# leds.net
KiCad netlist of a schematic drawn in EAGLE
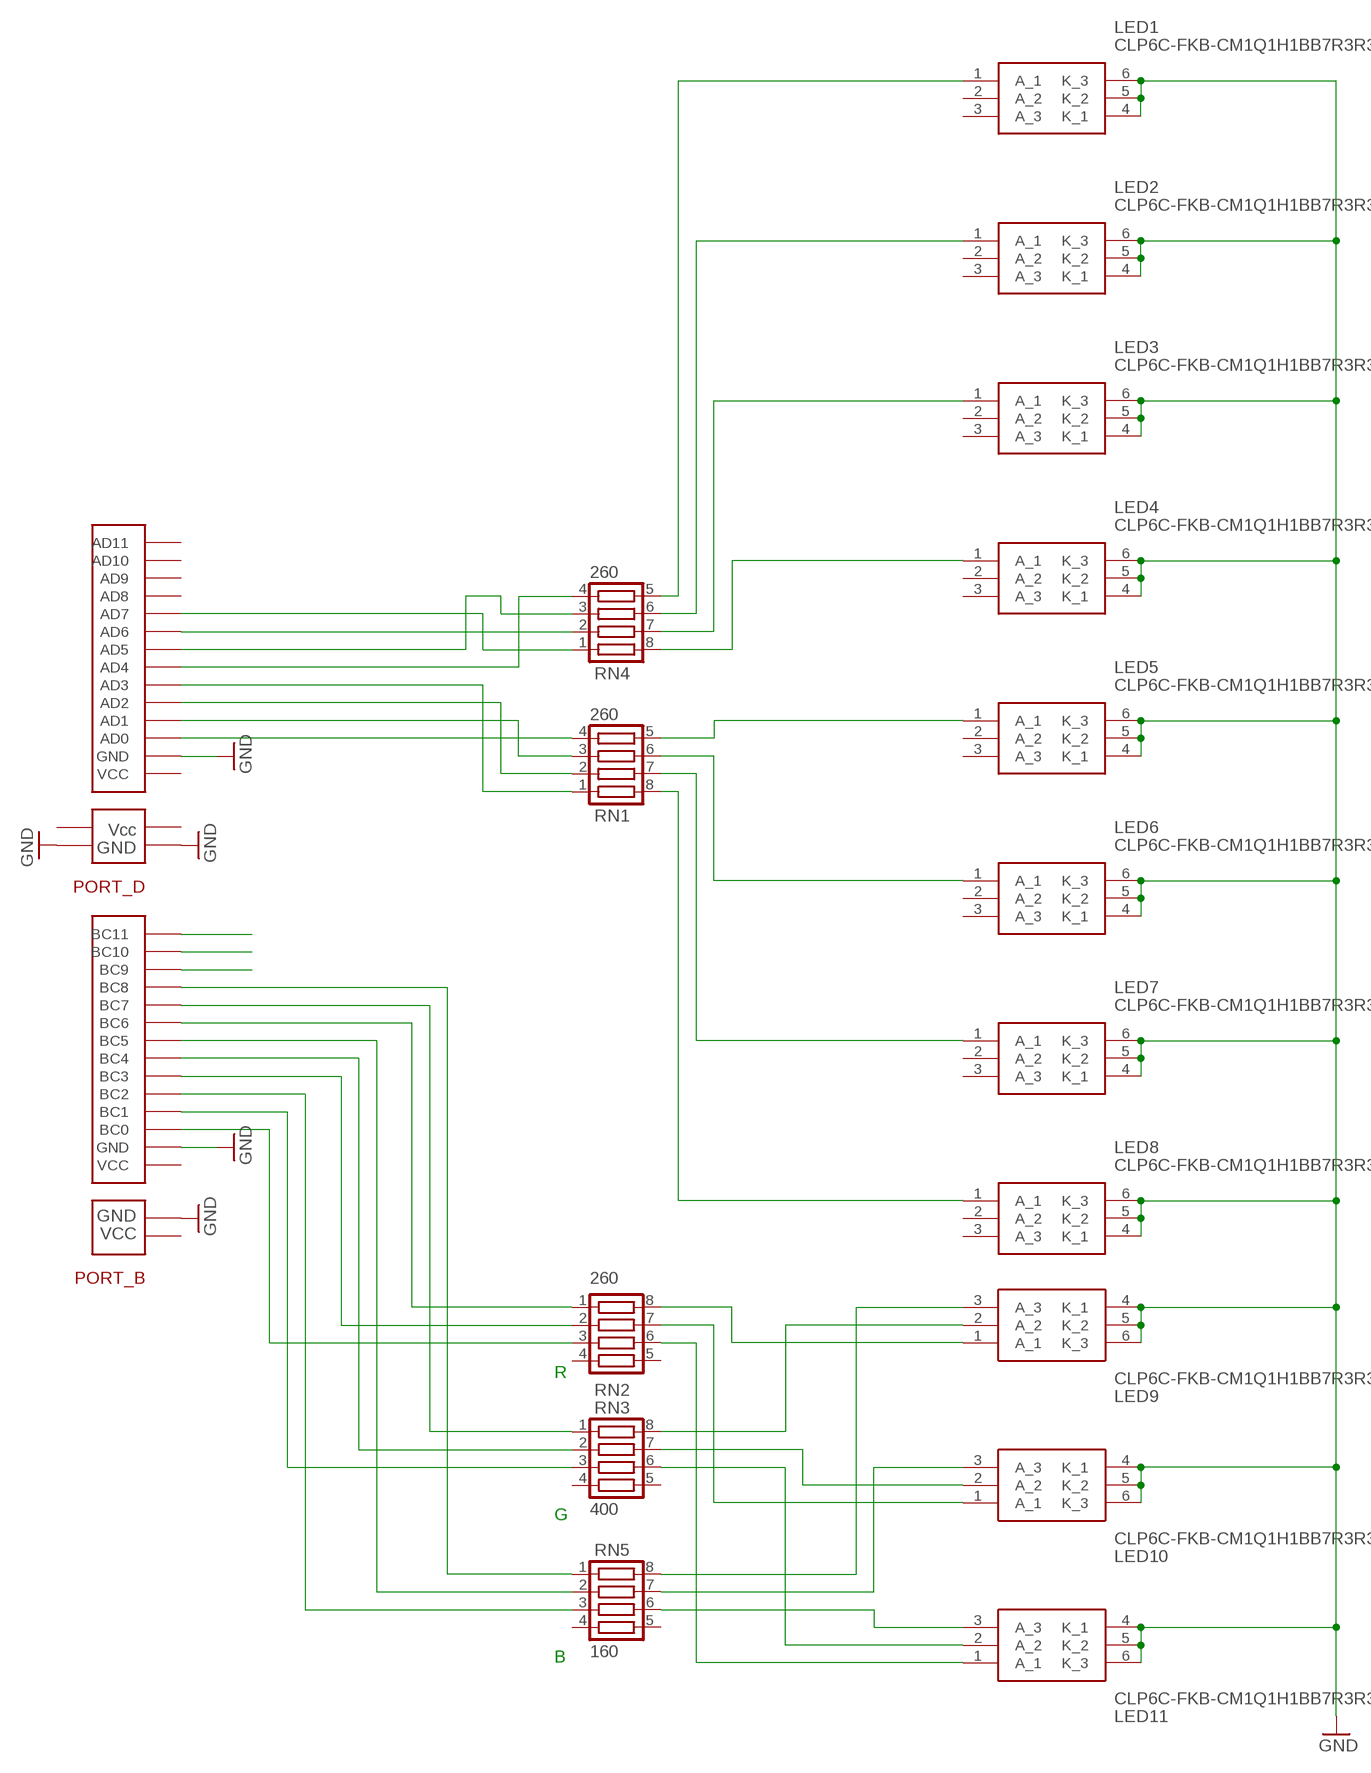
[diagram p0: schematic, sheet 1]

(export (version "E")
  (design (tool "Eeschema 10.0.6"))
  (components
    (comp (ref "LED1")
      (value "CLP6C-FKB-CM1Q1H1BB7R3R3")
      (footprint "eagle-import:CLP6CFKBCM1Q1H1BB7R3R3")
      (fields
        (field (name "MOUSER_PART_NUMBER") "941-P6CFKBCM1Q1H17R3")
        (field (name "RS_PART_NUMBER") "8106939P")
      )
      (libsource (lib "eagle-import") (part "CLP6C-FKB-CM1Q1H1BB7R3R3"))
    )
    (comp (ref "LED2")
      (value "CLP6C-FKB-CM1Q1H1BB7R3R3")
      (footprint "eagle-import:CLP6CFKBCM1Q1H1BB7R3R3")
      (fields
        (field (name "MOUSER_PART_NUMBER") "941-P6CFKBCM1Q1H17R3")
        (field (name "RS_PART_NUMBER") "8106939P")
      )
      (libsource (lib "eagle-import") (part "CLP6C-FKB-CM1Q1H1BB7R3R3"))
    )
    (comp (ref "LED3")
      (value "CLP6C-FKB-CM1Q1H1BB7R3R3")
      (footprint "eagle-import:CLP6CFKBCM1Q1H1BB7R3R3")
      (fields
        (field (name "MOUSER_PART_NUMBER") "941-P6CFKBCM1Q1H17R3")
        (field (name "RS_PART_NUMBER") "8106939P")
      )
      (libsource (lib "eagle-import") (part "CLP6C-FKB-CM1Q1H1BB7R3R3"))
    )
    (comp (ref "LED4")
      (value "CLP6C-FKB-CM1Q1H1BB7R3R3")
      (footprint "eagle-import:CLP6CFKBCM1Q1H1BB7R3R3")
      (fields
        (field (name "MOUSER_PART_NUMBER") "941-P6CFKBCM1Q1H17R3")
        (field (name "RS_PART_NUMBER") "8106939P")
      )
      (libsource (lib "eagle-import") (part "CLP6C-FKB-CM1Q1H1BB7R3R3"))
    )
    (comp (ref "LED5")
      (value "CLP6C-FKB-CM1Q1H1BB7R3R3")
      (footprint "eagle-import:CLP6CFKBCM1Q1H1BB7R3R3")
      (fields
        (field (name "MOUSER_PART_NUMBER") "941-P6CFKBCM1Q1H17R3")
        (field (name "RS_PART_NUMBER") "8106939P")
      )
      (libsource (lib "eagle-import") (part "CLP6C-FKB-CM1Q1H1BB7R3R3"))
    )
    (comp (ref "LED6")
      (value "CLP6C-FKB-CM1Q1H1BB7R3R3")
      (footprint "eagle-import:CLP6CFKBCM1Q1H1BB7R3R3")
      (fields
        (field (name "MOUSER_PART_NUMBER") "941-P6CFKBCM1Q1H17R3")
        (field (name "RS_PART_NUMBER") "8106939P")
      )
      (libsource (lib "eagle-import") (part "CLP6C-FKB-CM1Q1H1BB7R3R3"))
    )
    (comp (ref "LED7")
      (value "CLP6C-FKB-CM1Q1H1BB7R3R3")
      (footprint "eagle-import:CLP6CFKBCM1Q1H1BB7R3R3")
      (fields
        (field (name "MOUSER_PART_NUMBER") "941-P6CFKBCM1Q1H17R3")
        (field (name "RS_PART_NUMBER") "8106939P")
      )
      (libsource (lib "eagle-import") (part "CLP6C-FKB-CM1Q1H1BB7R3R3"))
    )
    (comp (ref "LED8")
      (value "CLP6C-FKB-CM1Q1H1BB7R3R3")
      (footprint "eagle-import:CLP6CFKBCM1Q1H1BB7R3R3")
      (fields
        (field (name "MOUSER_PART_NUMBER") "941-P6CFKBCM1Q1H17R3")
        (field (name "RS_PART_NUMBER") "8106939P")
      )
      (libsource (lib "eagle-import") (part "CLP6C-FKB-CM1Q1H1BB7R3R3"))
    )
    (comp (ref "LED9")
      (value "CLP6C-FKB-CM1Q1H1BB7R3R3")
      (footprint "eagle-import:CLP6CFKBCM1Q1H1BB7R3R3")
      (fields
        (field (name "MOUSER_PART_NUMBER") "941-P6CFKBCM1Q1H17R3")
        (field (name "RS_PART_NUMBER") "8106939P")
      )
      (libsource (lib "eagle-import") (part "CLP6C-FKB-CM1Q1H1BB7R3R3"))
    )
    (comp (ref "LED10")
      (value "CLP6C-FKB-CM1Q1H1BB7R3R3")
      (footprint "eagle-import:CLP6CFKBCM1Q1H1BB7R3R3")
      (fields
        (field (name "MOUSER_PART_NUMBER") "941-P6CFKBCM1Q1H17R3")
        (field (name "RS_PART_NUMBER") "8106939P")
      )
      (libsource (lib "eagle-import") (part "CLP6C-FKB-CM1Q1H1BB7R3R3"))
    )
    (comp (ref "LED11")
      (value "CLP6C-FKB-CM1Q1H1BB7R3R3")
      (footprint "eagle-import:CLP6CFKBCM1Q1H1BB7R3R3")
      (fields
        (field (name "MOUSER_PART_NUMBER") "941-P6CFKBCM1Q1H17R3")
        (field (name "RS_PART_NUMBER") "8106939P")
      )
      (libsource (lib "eagle-import") (part "CLP6C-FKB-CM1Q1H1BB7R3R3"))
    )
    (comp (ref "PORT_B")
      (value "PATICE_CERVENA")
      (footprint "eagle-import:PATICE_CERVENA")
      (libsource (lib "eagle-import") (part "PATICE_CERVENA"))
    )
    (comp (ref "PORT_D")
      (value "PATICE_ZELENA")
      (footprint "eagle-import:PATICE_ZELENA")
      (libsource (lib "eagle-import") (part "PATICE_ZELENA"))
    )
    (comp (ref "RN1")
      (value "260")
      (footprint "eagle-import:CTS742C083")
      (libsource (lib "eagle-import") (part "CTS742C083"))
    )
    (comp (ref "RN2")
      (value "260")
      (footprint "eagle-import:CTS742C083")
      (libsource (lib "eagle-import") (part "CTS742C083"))
    )
    (comp (ref "RN3")
      (value "400")
      (footprint "eagle-import:CTS742C083")
      (libsource (lib "eagle-import") (part "CTS742C083"))
    )
    (comp (ref "RN4")
      (value "260")
      (footprint "eagle-import:CTS742C083")
      (libsource (lib "eagle-import") (part "CTS742C083"))
    )
    (comp (ref "RN5")
      (value "160")
      (footprint "eagle-import:CTS742C083")
      (libsource (lib "eagle-import") (part "CTS742C083"))
    )
  )
  (nets
    (net (code "1") (name "GND") (class "Default")
      (node (ref "LED1") (pin "4") (pinfunction "K_1_4") (pintype "bidirectional"))
      (node (ref "LED1") (pin "5") (pinfunction "K_2_5") (pintype "bidirectional"))
      (node (ref "LED1") (pin "6") (pinfunction "K_3_6") (pintype "bidirectional"))
      (node (ref "LED10") (pin "4") (pinfunction "K_1_4") (pintype "bidirectional"))
      (node (ref "LED10") (pin "5") (pinfunction "K_2_5") (pintype "bidirectional"))
      (node (ref "LED10") (pin "6") (pinfunction "K_3_6") (pintype "bidirectional"))
      (node (ref "LED11") (pin "4") (pinfunction "K_1_4") (pintype "bidirectional"))
      (node (ref "LED11") (pin "5") (pinfunction "K_2_5") (pintype "bidirectional"))
      (node (ref "LED11") (pin "6") (pinfunction "K_3_6") (pintype "bidirectional"))
      (node (ref "LED2") (pin "4") (pinfunction "K_1_4") (pintype "bidirectional"))
      (node (ref "LED2") (pin "5") (pinfunction "K_2_5") (pintype "bidirectional"))
      (node (ref "LED2") (pin "6") (pinfunction "K_3_6") (pintype "bidirectional"))
      (node (ref "LED3") (pin "4") (pinfunction "K_1_4") (pintype "bidirectional"))
      (node (ref "LED3") (pin "5") (pinfunction "K_2_5") (pintype "bidirectional"))
      (node (ref "LED3") (pin "6") (pinfunction "K_3_6") (pintype "bidirectional"))
      (node (ref "LED4") (pin "4") (pinfunction "K_1_4") (pintype "bidirectional"))
      (node (ref "LED4") (pin "5") (pinfunction "K_2_5") (pintype "bidirectional"))
      (node (ref "LED4") (pin "6") (pinfunction "K_3_6") (pintype "bidirectional"))
      (node (ref "LED5") (pin "4") (pinfunction "K_1_4") (pintype "bidirectional"))
      (node (ref "LED5") (pin "5") (pinfunction "K_2_5") (pintype "bidirectional"))
      (node (ref "LED5") (pin "6") (pinfunction "K_3_6") (pintype "bidirectional"))
      (node (ref "LED6") (pin "4") (pinfunction "K_1_4") (pintype "bidirectional"))
      (node (ref "LED6") (pin "5") (pinfunction "K_2_5") (pintype "bidirectional"))
      (node (ref "LED6") (pin "6") (pinfunction "K_3_6") (pintype "bidirectional"))
      (node (ref "LED7") (pin "4") (pinfunction "K_1_4") (pintype "bidirectional"))
      (node (ref "LED7") (pin "5") (pinfunction "K_2_5") (pintype "bidirectional"))
      (node (ref "LED7") (pin "6") (pinfunction "K_3_6") (pintype "bidirectional"))
      (node (ref "LED8") (pin "4") (pinfunction "K_1_4") (pintype "bidirectional"))
      (node (ref "LED8") (pin "5") (pinfunction "K_2_5") (pintype "bidirectional"))
      (node (ref "LED8") (pin "6") (pinfunction "K_3_6") (pintype "bidirectional"))
      (node (ref "LED9") (pin "4") (pinfunction "K_1_4") (pintype "bidirectional"))
      (node (ref "LED9") (pin "5") (pinfunction "K_2_5") (pintype "bidirectional"))
      (node (ref "LED9") (pin "6") (pinfunction "K_3_6") (pintype "bidirectional"))
      (node (ref "PORT_B") (pin "GND") (pinfunction "GND_GND") (pintype "passive"))
      (node (ref "PORT_B") (pin "GND/") (pinfunction "GND_GND/") (pintype "passive"))
      (node (ref "PORT_D") (pin "GND") (pinfunction "GND_GND") (pintype "passive"))
      (node (ref "PORT_D") (pin "GND/") (pinfunction "GND_GND/") (pintype "passive"))
      (node (ref "PORT_D") (pin "GND//") (pinfunction "GND_GND//") (pintype "passive"))
    )
    (net (code "2") (name "Net-(LED1-A_1)") (class "Default")
      (node (ref "LED1") (pin "1") (pinfunction "A_1_1") (pintype "bidirectional"))
      (node (ref "RN4") (pin "5") (pinfunction "5_5") (pintype "passive"))
    )
    (net (code "3") (name "Net-(LED2-A_1)") (class "Default")
      (node (ref "LED2") (pin "1") (pinfunction "A_1_1") (pintype "bidirectional"))
      (node (ref "RN4") (pin "6") (pinfunction "6_6") (pintype "passive"))
    )
    (net (code "4") (name "Net-(LED3-A_1)") (class "Default")
      (node (ref "LED3") (pin "1") (pinfunction "A_1_1") (pintype "bidirectional"))
      (node (ref "RN4") (pin "7") (pinfunction "7_7") (pintype "passive"))
    )
    (net (code "5") (name "Net-(LED4-A_1)") (class "Default")
      (node (ref "LED4") (pin "1") (pinfunction "A_1_1") (pintype "bidirectional"))
      (node (ref "RN4") (pin "8") (pinfunction "8_8") (pintype "passive"))
    )
    (net (code "6") (name "Net-(LED5-A_1)") (class "Default")
      (node (ref "LED5") (pin "1") (pinfunction "A_1_1") (pintype "bidirectional"))
      (node (ref "RN1") (pin "5") (pinfunction "5_5") (pintype "passive"))
    )
    (net (code "7") (name "Net-(LED6-A_1)") (class "Default")
      (node (ref "LED6") (pin "1") (pinfunction "A_1_1") (pintype "bidirectional"))
      (node (ref "RN1") (pin "6") (pinfunction "6_6") (pintype "passive"))
    )
    (net (code "8") (name "Net-(LED7-A_1)") (class "Default")
      (node (ref "LED7") (pin "1") (pinfunction "A_1_1") (pintype "bidirectional"))
      (node (ref "RN1") (pin "7") (pinfunction "7_7") (pintype "passive"))
    )
    (net (code "9") (name "Net-(LED8-A_1)") (class "Default")
      (node (ref "LED8") (pin "1") (pinfunction "A_1_1") (pintype "bidirectional"))
      (node (ref "RN1") (pin "8") (pinfunction "8_8") (pintype "passive"))
    )
    (net (code "10") (name "Net-(LED9-A_1)") (class "Default")
      (node (ref "LED9") (pin "1") (pinfunction "A_1_1") (pintype "bidirectional"))
      (node (ref "RN2") (pin "8") (pinfunction "8_8") (pintype "passive"))
    )
    (net (code "11") (name "Net-(LED9-A_2)") (class "Default")
      (node (ref "LED9") (pin "2") (pinfunction "A_2_2") (pintype "bidirectional"))
      (node (ref "RN3") (pin "8") (pinfunction "8_8") (pintype "passive"))
    )
    (net (code "12") (name "Net-(LED9-A_3)") (class "Default")
      (node (ref "LED9") (pin "3") (pinfunction "A_3_3") (pintype "bidirectional"))
      (node (ref "RN5") (pin "8") (pinfunction "8_8") (pintype "passive"))
    )
    (net (code "13") (name "Net-(LED10-A_1)") (class "Default")
      (node (ref "LED10") (pin "1") (pinfunction "A_1_1") (pintype "bidirectional"))
      (node (ref "RN2") (pin "7") (pinfunction "7_7") (pintype "passive"))
    )
    (net (code "14") (name "Net-(LED10-A_2)") (class "Default")
      (node (ref "LED10") (pin "2") (pinfunction "A_2_2") (pintype "bidirectional"))
      (node (ref "RN3") (pin "7") (pinfunction "7_7") (pintype "passive"))
    )
    (net (code "15") (name "Net-(LED10-A_3)") (class "Default")
      (node (ref "LED10") (pin "3") (pinfunction "A_3_3") (pintype "bidirectional"))
      (node (ref "RN5") (pin "7") (pinfunction "7_7") (pintype "passive"))
    )
    (net (code "16") (name "Net-(LED11-A_1)") (class "Default")
      (node (ref "LED11") (pin "1") (pinfunction "A_1_1") (pintype "bidirectional"))
      (node (ref "RN2") (pin "6") (pinfunction "6_6") (pintype "passive"))
    )
    (net (code "17") (name "Net-(LED11-A_2)") (class "Default")
      (node (ref "LED11") (pin "2") (pinfunction "A_2_2") (pintype "bidirectional"))
      (node (ref "RN3") (pin "6") (pinfunction "6_6") (pintype "passive"))
    )
    (net (code "18") (name "Net-(LED11-A_3)") (class "Default")
      (node (ref "LED11") (pin "3") (pinfunction "A_3_3") (pintype "bidirectional"))
      (node (ref "RN5") (pin "6") (pinfunction "6_6") (pintype "passive"))
    )
    (net (code "19") (name "Net-(PORT_B-BC0)") (class "Default")
      (node (ref "PORT_B") (pin "CB0") (pinfunction "BC0_CB0") (pintype "bidirectional"))
      (node (ref "RN2") (pin "3") (pinfunction "3_3") (pintype "passive"))
    )
    (net (code "20") (name "Net-(PORT_B-BC1)") (class "Default")
      (node (ref "PORT_B") (pin "CB1") (pinfunction "BC1_CB1") (pintype "bidirectional"))
      (node (ref "RN3") (pin "3") (pinfunction "3_3") (pintype "passive"))
    )
    (net (code "21") (name "Net-(PORT_B-BC2)") (class "Default")
      (node (ref "PORT_B") (pin "CB2") (pinfunction "BC2_CB2") (pintype "bidirectional"))
      (node (ref "RN5") (pin "3") (pinfunction "3_3") (pintype "passive"))
    )
    (net (code "22") (name "Net-(PORT_B-BC3)") (class "Default")
      (node (ref "PORT_B") (pin "CB3") (pinfunction "BC3_CB3") (pintype "bidirectional"))
      (node (ref "RN2") (pin "2") (pinfunction "2_2") (pintype "passive"))
    )
    (net (code "23") (name "Net-(PORT_B-BC4)") (class "Default")
      (node (ref "PORT_B") (pin "CB4") (pinfunction "BC4_CB4") (pintype "bidirectional"))
      (node (ref "RN3") (pin "2") (pinfunction "2_2") (pintype "passive"))
    )
    (net (code "24") (name "Net-(PORT_B-BC5)") (class "Default")
      (node (ref "PORT_B") (pin "CB5") (pinfunction "BC5_CB5") (pintype "bidirectional"))
      (node (ref "RN5") (pin "2") (pinfunction "2_2") (pintype "passive"))
    )
    (net (code "25") (name "Net-(PORT_B-BC6)") (class "Default")
      (node (ref "PORT_B") (pin "CB6") (pinfunction "BC6_CB6") (pintype "bidirectional"))
      (node (ref "RN2") (pin "1") (pinfunction "1_1") (pintype "passive"))
    )
    (net (code "26") (name "Net-(PORT_B-BC7)") (class "Default")
      (node (ref "PORT_B") (pin "CB7") (pinfunction "BC7_CB7") (pintype "bidirectional"))
      (node (ref "RN3") (pin "1") (pinfunction "1_1") (pintype "passive"))
    )
    (net (code "27") (name "Net-(PORT_B-BC8)") (class "Default")
      (node (ref "PORT_B") (pin "CB8") (pinfunction "BC8_CB8") (pintype "bidirectional"))
      (node (ref "RN5") (pin "1") (pinfunction "1_1") (pintype "passive"))
    )
    (net (code "28") (name "Net-(PORT_D-PadAD0)") (class "Default")
      (node (ref "PORT_D") (pin "AD0") (pinfunction "AD0_AD0") (pintype "bidirectional"))
      (node (ref "RN1") (pin "4") (pinfunction "4_4") (pintype "passive"))
    )
    (net (code "29") (name "Net-(PORT_D-PadAD1)") (class "Default")
      (node (ref "PORT_D") (pin "AD1") (pinfunction "AD1_AD1") (pintype "bidirectional"))
      (node (ref "RN1") (pin "3") (pinfunction "3_3") (pintype "passive"))
    )
    (net (code "30") (name "Net-(PORT_D-PadAD2)") (class "Default")
      (node (ref "PORT_D") (pin "AD2") (pinfunction "AD2_AD2") (pintype "bidirectional"))
      (node (ref "RN1") (pin "2") (pinfunction "2_2") (pintype "passive"))
    )
    (net (code "31") (name "Net-(PORT_D-PadAD3)") (class "Default")
      (node (ref "PORT_D") (pin "AD3") (pinfunction "AD3_AD3") (pintype "bidirectional"))
      (node (ref "RN1") (pin "1") (pinfunction "1_1") (pintype "passive"))
    )
    (net (code "32") (name "Net-(PORT_D-PadAD4)") (class "Default")
      (node (ref "PORT_D") (pin "AD4") (pinfunction "AD4_AD4") (pintype "bidirectional"))
      (node (ref "RN4") (pin "4") (pinfunction "4_4") (pintype "passive"))
    )
    (net (code "33") (name "Net-(PORT_D-PadAD5)") (class "Default")
      (node (ref "PORT_D") (pin "AD5") (pinfunction "AD5_AD5") (pintype "bidirectional"))
      (node (ref "RN4") (pin "3") (pinfunction "3_3") (pintype "passive"))
    )
    (net (code "34") (name "Net-(PORT_D-PadAD6)") (class "Default")
      (node (ref "PORT_D") (pin "AD6") (pinfunction "AD6_AD6") (pintype "bidirectional"))
      (node (ref "RN4") (pin "2") (pinfunction "2_2") (pintype "passive"))
    )
    (net (code "35") (name "Net-(PORT_D-PadAD7)") (class "Default")
      (node (ref "PORT_D") (pin "AD7") (pinfunction "AD7_AD7") (pintype "bidirectional"))
      (node (ref "RN4") (pin "1") (pinfunction "1_1") (pintype "passive"))
    )
    (net (code "36") (name "unconnected-(LED1-A_2-Pad2)") (class "Default")
      (node (ref "LED1") (pin "2") (pinfunction "A_2_2") (pintype "bidirectional"))
    )
    (net (code "37") (name "unconnected-(LED1-A_3-Pad3)") (class "Default")
      (node (ref "LED1") (pin "3") (pinfunction "A_3_3") (pintype "bidirectional"))
    )
    (net (code "38") (name "unconnected-(LED2-A_2-Pad2)") (class "Default")
      (node (ref "LED2") (pin "2") (pinfunction "A_2_2") (pintype "bidirectional"))
    )
    (net (code "39") (name "unconnected-(LED2-A_3-Pad3)") (class "Default")
      (node (ref "LED2") (pin "3") (pinfunction "A_3_3") (pintype "bidirectional"))
    )
    (net (code "40") (name "unconnected-(LED3-A_2-Pad2)") (class "Default")
      (node (ref "LED3") (pin "2") (pinfunction "A_2_2") (pintype "bidirectional"))
    )
    (net (code "41") (name "unconnected-(LED3-A_3-Pad3)") (class "Default")
      (node (ref "LED3") (pin "3") (pinfunction "A_3_3") (pintype "bidirectional"))
    )
    (net (code "42") (name "unconnected-(LED4-A_2-Pad2)") (class "Default")
      (node (ref "LED4") (pin "2") (pinfunction "A_2_2") (pintype "bidirectional"))
    )
    (net (code "43") (name "unconnected-(LED4-A_3-Pad3)") (class "Default")
      (node (ref "LED4") (pin "3") (pinfunction "A_3_3") (pintype "bidirectional"))
    )
    (net (code "44") (name "unconnected-(LED5-A_2-Pad2)") (class "Default")
      (node (ref "LED5") (pin "2") (pinfunction "A_2_2") (pintype "bidirectional"))
    )
    (net (code "45") (name "unconnected-(LED5-A_3-Pad3)") (class "Default")
      (node (ref "LED5") (pin "3") (pinfunction "A_3_3") (pintype "bidirectional"))
    )
    (net (code "46") (name "unconnected-(LED6-A_2-Pad2)") (class "Default")
      (node (ref "LED6") (pin "2") (pinfunction "A_2_2") (pintype "bidirectional"))
    )
    (net (code "47") (name "unconnected-(LED6-A_3-Pad3)") (class "Default")
      (node (ref "LED6") (pin "3") (pinfunction "A_3_3") (pintype "bidirectional"))
    )
    (net (code "48") (name "unconnected-(LED7-A_2-Pad2)") (class "Default")
      (node (ref "LED7") (pin "2") (pinfunction "A_2_2") (pintype "bidirectional"))
    )
    (net (code "49") (name "unconnected-(LED7-A_3-Pad3)") (class "Default")
      (node (ref "LED7") (pin "3") (pinfunction "A_3_3") (pintype "bidirectional"))
    )
    (net (code "50") (name "unconnected-(LED8-A_2-Pad2)") (class "Default")
      (node (ref "LED8") (pin "2") (pinfunction "A_2_2") (pintype "bidirectional"))
    )
    (net (code "51") (name "unconnected-(LED8-A_3-Pad3)") (class "Default")
      (node (ref "LED8") (pin "3") (pinfunction "A_3_3") (pintype "bidirectional"))
    )
    (net (code "52") (name "unconnected-(PORT_B-BC9-PadCB9)") (class "Default")
      (node (ref "PORT_B") (pin "CB9") (pinfunction "BC9_CB9") (pintype "bidirectional"))
    )
    (net (code "53") (name "unconnected-(PORT_B-BC10-PadCB10)") (class "Default")
      (node (ref "PORT_B") (pin "CB10") (pinfunction "BC10_CB10") (pintype "bidirectional"))
    )
    (net (code "54") (name "unconnected-(PORT_B-BC11-PadCB11)") (class "Default")
      (node (ref "PORT_B") (pin "CB11") (pinfunction "BC11_CB11") (pintype "bidirectional"))
    )
    (net (code "55") (name "unconnected-(PORT_B-PadVCC)") (class "Default")
      (node (ref "PORT_B") (pin "VCC") (pinfunction "VCC_VCC") (pintype "passive"))
    )
    (net (code "56") (name "unconnected-(PORT_B-VCC-PadVCC{slash})") (class "Default")
      (node (ref "PORT_B") (pin "VCC/") (pinfunction "VCC_VCC/") (pintype "passive"))
    )
    (net (code "57") (name "unconnected-(PORT_D-PadAD8)") (class "Default")
      (node (ref "PORT_D") (pin "AD8") (pinfunction "AD8_AD8") (pintype "bidirectional"))
    )
    (net (code "58") (name "unconnected-(PORT_D-PadAD9)") (class "Default")
      (node (ref "PORT_D") (pin "AD9") (pinfunction "AD9_AD9") (pintype "bidirectional"))
    )
    (net (code "59") (name "unconnected-(PORT_D-PadAD10)") (class "Default")
      (node (ref "PORT_D") (pin "AD10") (pinfunction "AD10_AD10") (pintype "bidirectional"))
    )
    (net (code "60") (name "unconnected-(PORT_D-PadAD11)") (class "Default")
      (node (ref "PORT_D") (pin "AD11") (pinfunction "AD11_AD11") (pintype "bidirectional"))
    )
    (net (code "61") (name "unconnected-(PORT_D-PadVCC)") (class "Default")
      (node (ref "PORT_D") (pin "VCC") (pinfunction "VCC_VCC") (pintype "passive"))
    )
    (net (code "62") (name "unconnected-(PORT_D-VCC-PadVCC{slash})") (class "Default")
      (node (ref "PORT_D") (pin "VCC/") (pinfunction "VCC_VCC/") (pintype "passive"))
    )
    (net (code "63") (name "unconnected-(PORT_D-VCC-PadVCC{slash}{slash})") (class "Default")
      (node (ref "PORT_D") (pin "VCC//") (pinfunction "VCC_VCC//") (pintype "passive"))
    )
    (net (code "64") (name "unconnected-(RN2-Pad4)") (class "Default")
      (node (ref "RN2") (pin "4") (pinfunction "4_4") (pintype "passive"))
    )
    (net (code "65") (name "unconnected-(RN2-Pad5)") (class "Default")
      (node (ref "RN2") (pin "5") (pinfunction "5_5") (pintype "passive"))
    )
    (net (code "66") (name "unconnected-(RN3-Pad4)") (class "Default")
      (node (ref "RN3") (pin "4") (pinfunction "4_4") (pintype "passive"))
    )
    (net (code "67") (name "unconnected-(RN3-Pad5)") (class "Default")
      (node (ref "RN3") (pin "5") (pinfunction "5_5") (pintype "passive"))
    )
    (net (code "68") (name "unconnected-(RN5-Pad4)") (class "Default")
      (node (ref "RN5") (pin "4") (pinfunction "4_4") (pintype "passive"))
    )
    (net (code "69") (name "unconnected-(RN5-Pad5)") (class "Default")
      (node (ref "RN5") (pin "5") (pinfunction "5_5") (pintype "passive"))
    )
  )
)
